# converter.net
KiCad netlist of a schematic drawn in Altium Designer
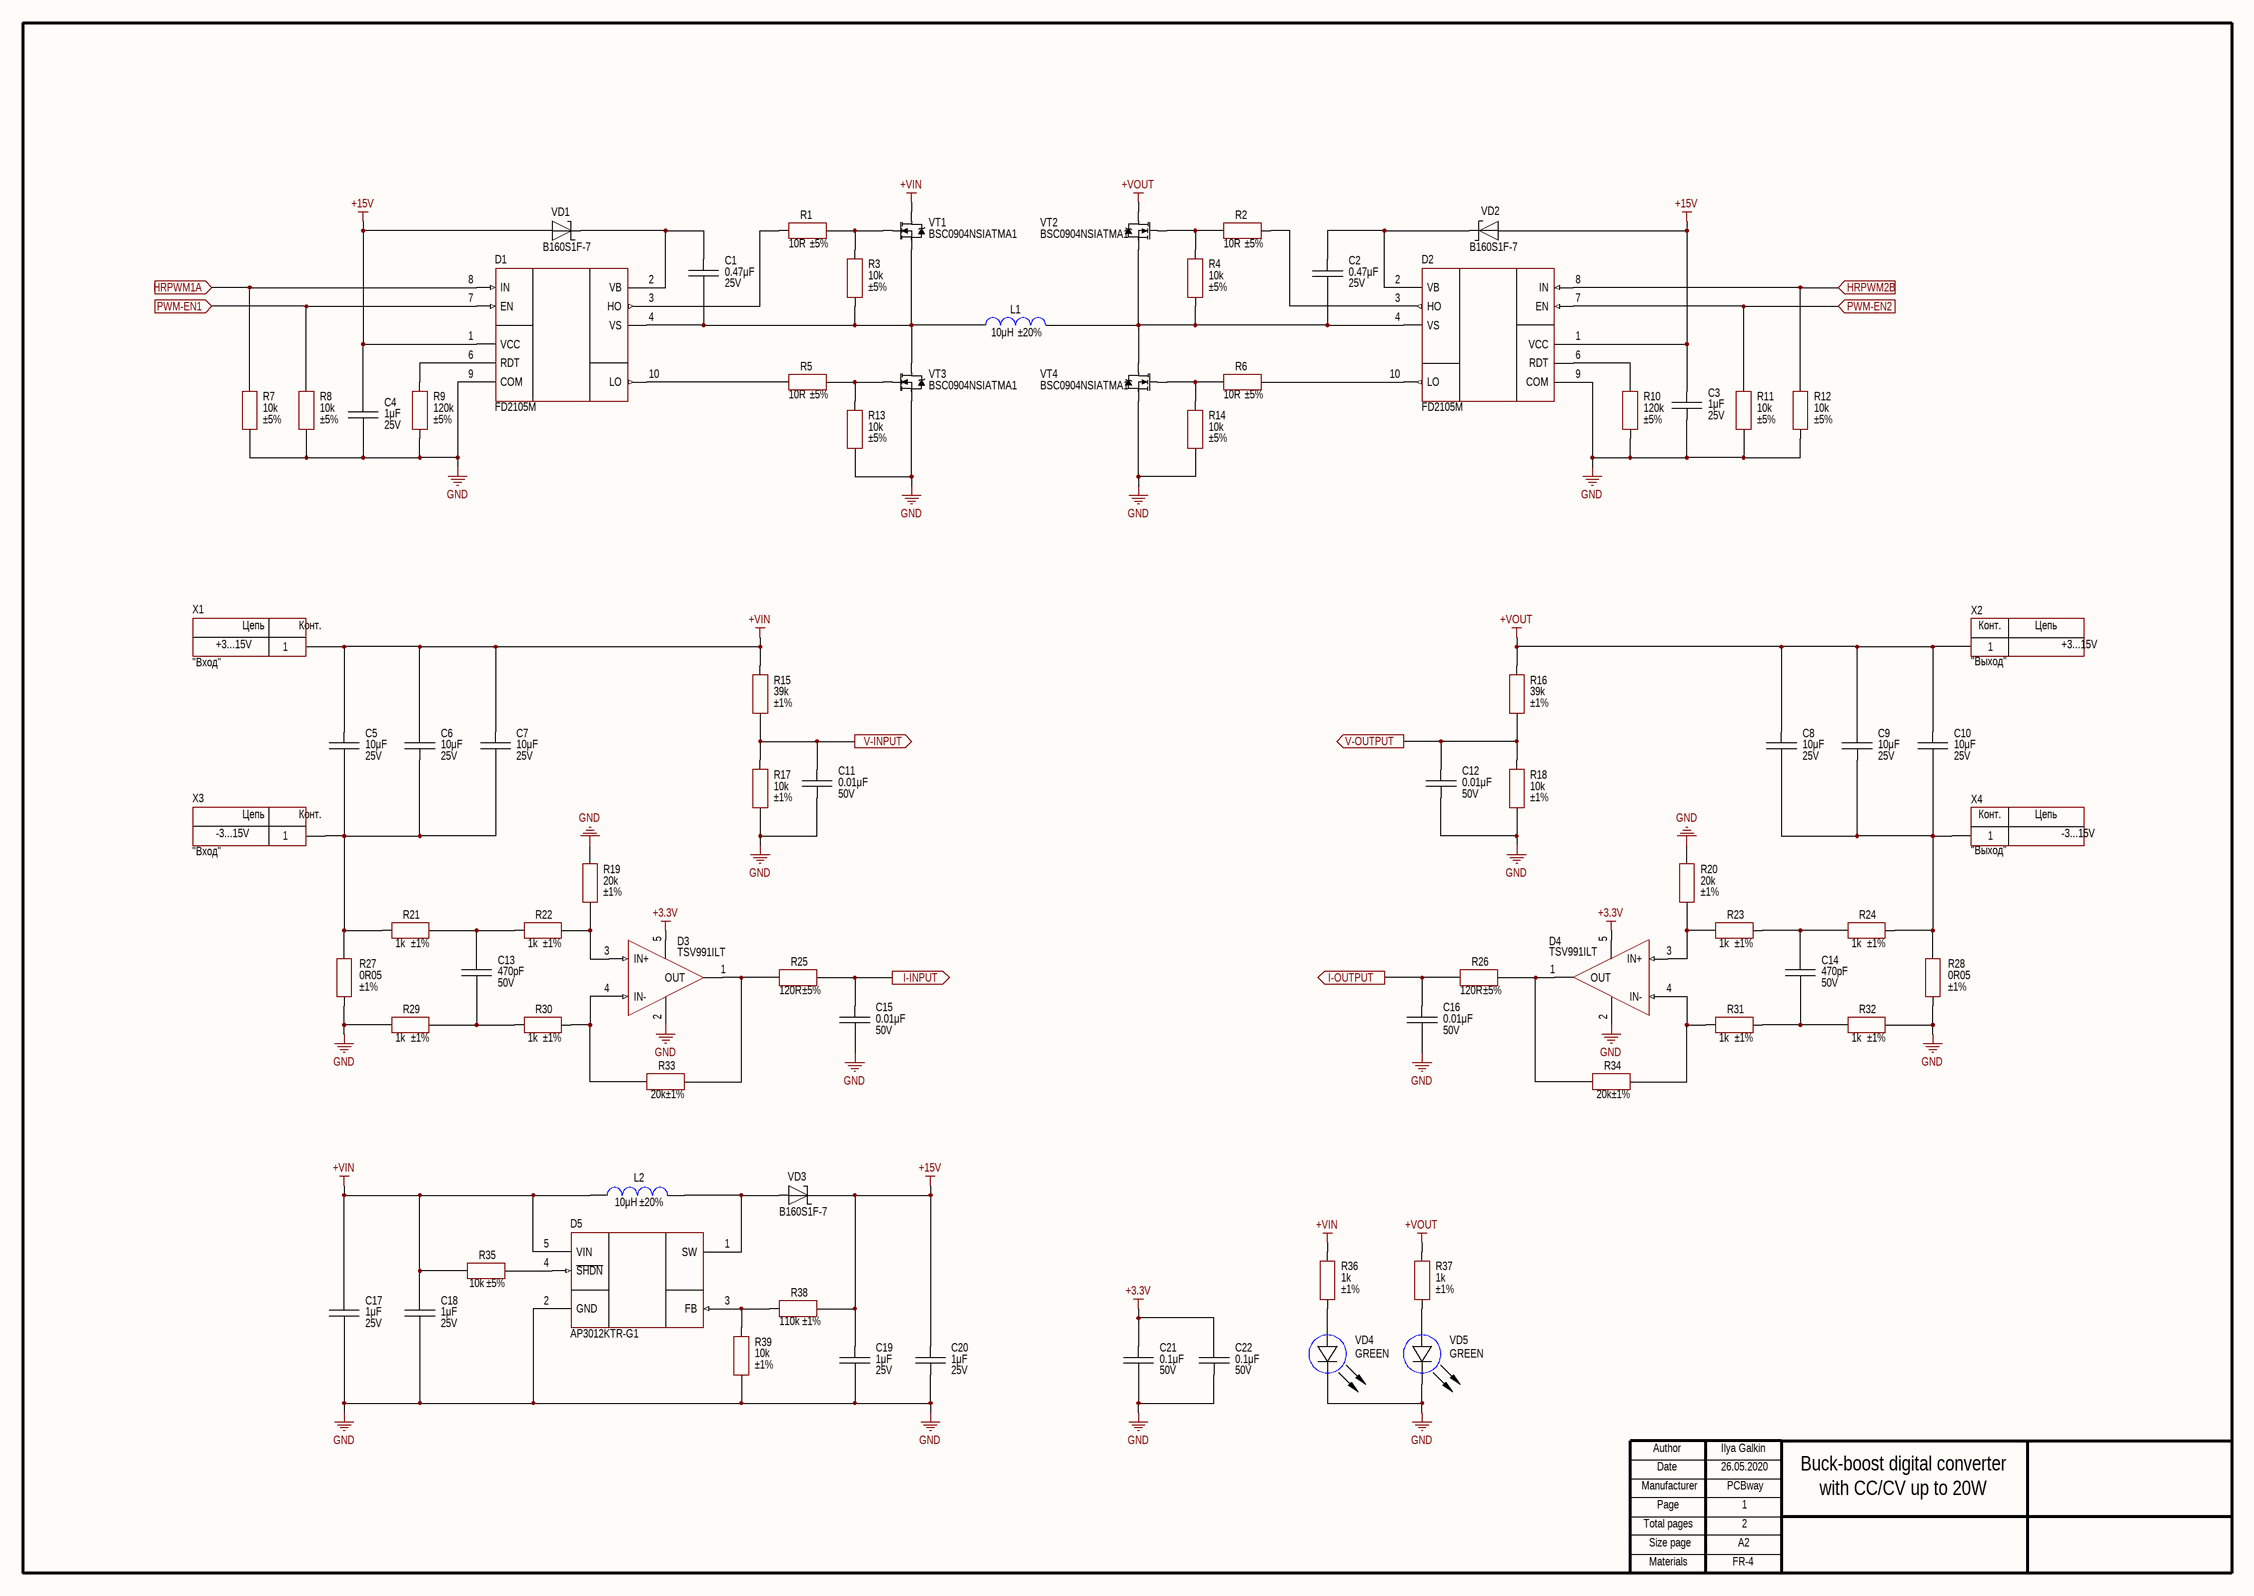
[diagram p0: converter.SchDoc]

(export (version "E")
  (design (tool "Eeschema 10.0.6"))
  (components
    (comp (ref "C1")
      (value "0.47μF")
      (footprint "CAP: 0805")
      (fields
        (field (name "MANUFACTURER") "Samsung")
        (field (name "PARTNUMBER") "CL21B474KAFNNNG")
        (field (name "VALUEMANUFACTURERPARTNUMBER") "Ceramic capacitor, 0.47μF, X7R, ±10%, 25V, 0805, -55...+125°C")
        (field (name "VOLTAGE") "25V")
      )
      (libsource (lib "Capacitor") (part "Ceramic_0805"))
    )
    (comp (ref "C2")
      (value "0.47μF")
      (footprint "CAP: 0805")
      (fields
        (field (name "MANUFACTURER") "Samsung")
        (field (name "PARTNUMBER") "CL21B474KAFNNNG")
        (field (name "VALUEMANUFACTURERPARTNUMBER") "Ceramic capacitor, 0.47μF, X7R, ±10%, 25V, 0805, -55...+125°C")
        (field (name "VOLTAGE") "25V")
      )
      (libsource (lib "Capacitor") (part "Ceramic_0805"))
    )
    (comp (ref "C3")
      (value "1μF")
      (footprint "CAP: 0603")
      (fields
        (field (name "MANUFACTURER") "Samsung")
        (field (name "PARTNUMBER") "CL10B105KA8NNNC")
        (field (name "VALUEMANUFACTURERPARTNUMBER") "Ceramic capacitor, 1μF, X7R, ±10%, 25V, 0603, -55...+125°C")
        (field (name "VOLTAGE") "25V")
      )
      (libsource (lib "Capacitor") (part "Ceramic_0603"))
    )
    (comp (ref "C4")
      (value "1μF")
      (footprint "CAP: 0603")
      (fields
        (field (name "MANUFACTURER") "Samsung")
        (field (name "PARTNUMBER") "CL10B105KA8NNNC")
        (field (name "VALUEMANUFACTURERPARTNUMBER") "Ceramic capacitor, 1μF, X7R, ±10%, 25V, 0603, -55...+125°C")
        (field (name "VOLTAGE") "25V")
      )
      (libsource (lib "Capacitor") (part "Ceramic_0603"))
    )
    (comp (ref "C5")
      (value "10μF")
      (footprint "CAP: 1210")
      (fields
        (field (name "MANUFACTURER") "Samsung")
        (field (name "PARTNUMBER") "CL32B106KAJNNNE")
        (field (name "VALUEMANUFACTURERPARTNUMBER") "Ceramic capacitor, 10μF, X7R, ±10%, 25V, 1210, -55...+125°C")
        (field (name "VOLTAGE") "25V")
      )
      (libsource (lib "Capacitor") (part "Ceramic_1210"))
    )
    (comp (ref "C6")
      (value "10μF")
      (footprint "CAP: 1210")
      (fields
        (field (name "MANUFACTURER") "Samsung")
        (field (name "PARTNUMBER") "CL32B106KAJNNNE")
        (field (name "VALUEMANUFACTURERPARTNUMBER") "Ceramic capacitor, 10μF, X7R, ±10%, 25V, 1210, -55...+125°C")
        (field (name "VOLTAGE") "25V")
      )
      (libsource (lib "Capacitor") (part "Ceramic_1210"))
    )
    (comp (ref "C7")
      (value "10μF")
      (footprint "CAP: 1210")
      (fields
        (field (name "MANUFACTURER") "Samsung")
        (field (name "PARTNUMBER") "CL32B106KAJNNNE")
        (field (name "VALUEMANUFACTURERPARTNUMBER") "Ceramic capacitor, 10μF, X7R, ±10%, 25V, 1210, -55...+125°C")
        (field (name "VOLTAGE") "25V")
      )
      (libsource (lib "Capacitor") (part "Ceramic_1210"))
    )
    (comp (ref "C8")
      (value "10μF")
      (footprint "CAP: 1210")
      (fields
        (field (name "MANUFACTURER") "Samsung")
        (field (name "PARTNUMBER") "CL32B106KAJNNNE")
        (field (name "VALUEMANUFACTURERPARTNUMBER") "Ceramic capacitor, 10μF, X7R, ±10%, 25V, 1210, -55...+125°C")
        (field (name "VOLTAGE") "25V")
      )
      (libsource (lib "Capacitor") (part "Ceramic_1210"))
    )
    (comp (ref "C9")
      (value "10μF")
      (footprint "CAP: 1210")
      (fields
        (field (name "MANUFACTURER") "Samsung")
        (field (name "PARTNUMBER") "CL32B106KAJNNNE")
        (field (name "VALUEMANUFACTURERPARTNUMBER") "Ceramic capacitor, 10μF, X7R, ±10%, 25V, 1210, -55...+125°C")
        (field (name "VOLTAGE") "25V")
      )
      (libsource (lib "Capacitor") (part "Ceramic_1210"))
    )
    (comp (ref "C10")
      (value "10μF")
      (footprint "CAP: 1210")
      (fields
        (field (name "MANUFACTURER") "Samsung")
        (field (name "PARTNUMBER") "CL32B106KAJNNNE")
        (field (name "VALUEMANUFACTURERPARTNUMBER") "Ceramic capacitor, 10μF, X7R, ±10%, 25V, 1210, -55...+125°C")
        (field (name "VOLTAGE") "25V")
      )
      (libsource (lib "Capacitor") (part "Ceramic_1210"))
    )
    (comp (ref "C11")
      (value "0.01μF")
      (footprint "CAP: 0603")
      (fields
        (field (name "MANUFACTURER") "Yageo")
        (field (name "PARTNUMBER") "CL10B103KB8NNNC")
        (field (name "VALUEMANUFACTURERPARTNUMBER") "Ceramic capacitor, 0.01μF, X7R, ±10%, 50V, 0603, -55...+125°C")
        (field (name "VOLTAGE") "50V")
      )
      (libsource (lib "Capacitor") (part "Ceramic_0603"))
    )
    (comp (ref "C12")
      (value "0.01μF")
      (footprint "CAP: 0603")
      (fields
        (field (name "MANUFACTURER") "Yageo")
        (field (name "PARTNUMBER") "CL10B103KB8NNNC")
        (field (name "VALUEMANUFACTURERPARTNUMBER") "Ceramic capacitor, 0.01μF, X7R, ±10%, 50V, 0603, -55...+125°C")
        (field (name "VOLTAGE") "50V")
      )
      (libsource (lib "Capacitor") (part "Ceramic_0603"))
    )
    (comp (ref "C13")
      (value "470pF")
      (footprint "CAP: 0603")
      (fields
        (field (name "MANUFACTURER") "Yageo")
        (field (name "PARTNUMBER") "CL10C471JB8NNNC")
        (field (name "VALUEMANUFACTURERPARTNUMBER") "Ceramic capacitor, 470pF, NPO, ±5%, 50V, 0603, -55...+125°C")
        (field (name "VOLTAGE") "50V")
      )
      (libsource (lib "Capacitor") (part "Ceramic_0603"))
    )
    (comp (ref "C14")
      (value "470pF")
      (footprint "CAP: 0603")
      (fields
        (field (name "MANUFACTURER") "Yageo")
        (field (name "PARTNUMBER") "CL10C471JB8NNNC")
        (field (name "VALUEMANUFACTURERPARTNUMBER") "Ceramic capacitor, 470pF, NPO, ±5%, 50V, 0603, -55...+125°C")
        (field (name "VOLTAGE") "50V")
      )
      (libsource (lib "Capacitor") (part "Ceramic_0603"))
    )
    (comp (ref "C15")
      (value "0.01μF")
      (footprint "CAP: 0603")
      (fields
        (field (name "MANUFACTURER") "Yageo")
        (field (name "PARTNUMBER") "CL10B103KB8NNNC")
        (field (name "VALUEMANUFACTURERPARTNUMBER") "Ceramic capacitor, 0.01μF, X7R, ±10%, 50V, 0603, -55...+125°C")
        (field (name "VOLTAGE") "50V")
      )
      (libsource (lib "Capacitor") (part "Ceramic_0603"))
    )
    (comp (ref "C16")
      (value "0.01μF")
      (footprint "CAP: 0603")
      (fields
        (field (name "MANUFACTURER") "Yageo")
        (field (name "PARTNUMBER") "CL10B103KB8NNNC")
        (field (name "VALUEMANUFACTURERPARTNUMBER") "Ceramic capacitor, 0.01μF, X7R, ±10%, 50V, 0603, -55...+125°C")
        (field (name "VOLTAGE") "50V")
      )
      (libsource (lib "Capacitor") (part "Ceramic_0603"))
    )
    (comp (ref "C17")
      (value "1μF")
      (footprint "CAP: 0603")
      (fields
        (field (name "MANUFACTURER") "Samsung")
        (field (name "PARTNUMBER") "CL10B105KA8NNNC")
        (field (name "VALUEMANUFACTURERPARTNUMBER") "Ceramic capacitor, 1μF, X7R, ±10%, 25V, 0603, -55...+125°C")
        (field (name "VOLTAGE") "25V")
      )
      (libsource (lib "Capacitor") (part "Ceramic_0603"))
    )
    (comp (ref "C18")
      (value "1μF")
      (footprint "CAP: 0603")
      (fields
        (field (name "MANUFACTURER") "Samsung")
        (field (name "PARTNUMBER") "CL10B105KA8NNNC")
        (field (name "VALUEMANUFACTURERPARTNUMBER") "Ceramic capacitor, 1μF, X7R, ±10%, 25V, 0603, -55...+125°C")
        (field (name "VOLTAGE") "25V")
      )
      (libsource (lib "Capacitor") (part "Ceramic_0603"))
    )
    (comp (ref "C19")
      (value "1μF")
      (footprint "CAP: 0603")
      (fields
        (field (name "MANUFACTURER") "Samsung")
        (field (name "PARTNUMBER") "CL10B105KA8NNNC")
        (field (name "VALUEMANUFACTURERPARTNUMBER") "Ceramic capacitor, 1μF, X7R, ±10%, 25V, 0603, -55...+125°C")
        (field (name "VOLTAGE") "25V")
      )
      (libsource (lib "Capacitor") (part "Ceramic_0603"))
    )
    (comp (ref "C20")
      (value "1μF")
      (footprint "CAP: 0603")
      (fields
        (field (name "MANUFACTURER") "Samsung")
        (field (name "PARTNUMBER") "CL10B105KA8NNNC")
        (field (name "VALUEMANUFACTURERPARTNUMBER") "Ceramic capacitor, 1μF, X7R, ±10%, 25V, 0603, -55...+125°C")
        (field (name "VOLTAGE") "25V")
      )
      (libsource (lib "Capacitor") (part "Ceramic_0603"))
    )
    (comp (ref "C21")
      (value "0.1μF")
      (footprint "CAP: 0603")
      (fields
        (field (name "MANUFACTURER") "Yageo")
        (field (name "PARTNUMBER") "CL10B104KB8WPND")
        (field (name "VALUEMANUFACTURERPARTNUMBER") "Ceramic capacitor, 0.1μF, X7R, ±10%, 50V, 0603, -55...+125°C")
        (field (name "VOLTAGE") "50V")
      )
      (libsource (lib "Capacitor") (part "Ceramic_0603"))
    )
    (comp (ref "C22")
      (value "0.1μF")
      (footprint "CAP: 0603")
      (fields
        (field (name "MANUFACTURER") "Yageo")
        (field (name "PARTNUMBER") "CL10B104KB8WPND")
        (field (name "VALUEMANUFACTURERPARTNUMBER") "Ceramic capacitor, 0.1μF, X7R, ±10%, 50V, 0603, -55...+125°C")
        (field (name "VOLTAGE") "50V")
      )
      (libsource (lib "Capacitor") (part "Ceramic_0603"))
    )
    (comp (ref "D1")
      (value "~")
      (footprint "10-TSSOP")
      (description "Gate driver")
      (fields
        (field (name "MANUFACTURER") "Fortior Tech")
        (field (name "VALUEMANUFACTURERPARTNUMBER") "Half-bridge gate driver, 40V, +1.2A/-1.8A, Complementary, supply 3...21V, -40...+125°C, 10-MSOP")
        (field (name "PARTNUMBER") "FD2105M")
      )
      (libsource (lib "") (part "FD2105M_1"))
    )
    (comp (ref "D2")
      (value "~")
      (footprint "10-TSSOP")
      (description "Gate driver")
      (fields
        (field (name "MANUFACTURER") "Fortior Tech")
        (field (name "VALUEMANUFACTURERPARTNUMBER") "Half-bridge gate driver, 40V, +1.2A/-1.8A, Complementary, supply 3...21V, -40...+125°C, 10-MSOP")
        (field (name "PARTNUMBER") "FD2105M")
      )
      (libsource (lib "IC. Gate driver") (part "FD2105M"))
    )
    (comp (ref "D3")
      (value "~")
      (footprint "SOT23-5")
      (description "OP amplifier")
      (fields
        (field (name "MANUFACTURER") "STMicroelectronics")
        (field (name "VALUEMANUFACTURERPARTNUMBER") "IC op amplifier, Rail-to-Rail, 20 MHz, 2.7...5.5V, -40...+125°C, SOT23-5")
        (field (name "PARTNUMBER") "TSV991ILT")
      )
      (libsource (lib "IC. Amplifier") (part "TSV991ILT"))
    )
    (comp (ref "D4")
      (value "~")
      (footprint "SOT23-5")
      (description "OP amplifier")
      (fields
        (field (name "MANUFACTURER") "STMicroelectronics")
        (field (name "VALUEMANUFACTURERPARTNUMBER") "IC op amplifier, Rail-to-Rail, 20 MHz, 2.7...5.5V, -40...+125°C, SOT23-5")
        (field (name "PARTNUMBER") "TSV991ILT")
      )
      (libsource (lib "IC. Amplifier") (part "TSV991ILT"))
    )
    (comp (ref "D5")
      (value "~")
      (footprint "SOT23-5")
      (description "Boost converter")
      (fields
        (field (name "MANUFACTURER") "Diodes Incorporated")
        (field (name "VALUEMANUFACTURERPARTNUMBER") "DC/DC boost converter, input 2.6...16V, 1.5MHz, output 3...29V, 0.5A, -40...+85°C, SOT23-5")
        (field (name "PARTNUMBER") "AP3012KTR-G1")
      )
      (libsource (lib "IC. Power supply") (part "AP3012KTR-G1"))
    )
    (comp (ref "L1")
      (value "10μH")
      (footprint "IND: SRP1038C")
      (fields
        (field (name "MANUFACTURER") "Bourns")
        (field (name "PARTNUMBER") "SRP1038C-100M")
        (field (name "VALUEMANUFACTURERPARTNUMBER") "Fixed inductor, 10μH, ±20%, SRP1038C, 8.5A, -40...+125°C")
        (field (name "TOLERANCE") "±20%")
      )
      (libsource (lib "Inductor") (part "Inductor_SRP1038C"))
    )
    (comp (ref "L2")
      (value "10μH")
      (footprint "IND: SDR0403")
      (fields
        (field (name "MANUFACTURER") "Bourns")
        (field (name "PARTNUMBER") "SDR0403-100ML")
        (field (name "VALUEMANUFACTURERPARTNUMBER") "Fixed inductor, 10μH, ±20%, SDR0403, 1.15A, -40...+125°C")
        (field (name "TOLERANCE") "±20%")
      )
      (libsource (lib "Inductor") (part "Inductor_SDR0403"))
    )
    (comp (ref "R1")
      (value "10R")
      (footprint "RES: 0603")
      (fields
        (field (name "MANUFACTURER") "Yageo")
        (field (name "PARTNUMBER") "RC0603JR-0710RL")
        (field (name "VALUEMANUFACTURERPARTNUMBER") "Resistor film, 10R, ±5%, 0603, 0.1W, -55...+125°C")
        (field (name "TOLERANCE") "±5%")
      )
      (libsource (lib "") (part "Resistor_0603_2"))
    )
    (comp (ref "R2")
      (value "10R")
      (footprint "RES: 0603")
      (fields
        (field (name "MANUFACTURER") "Yageo")
        (field (name "PARTNUMBER") "RC0603JR-0710RL")
        (field (name "VALUEMANUFACTURERPARTNUMBER") "Resistor film, 10R, ±5%, 0603, 0.1W, -55...+125°C")
        (field (name "TOLERANCE") "±5%")
      )
      (libsource (lib "") (part "Resistor_0603_2"))
    )
    (comp (ref "R3")
      (value "10k")
      (footprint "RES: 0603")
      (fields
        (field (name "MANUFACTURER") "Yageo")
        (field (name "PARTNUMBER") "RC0603JR-0710KL")
        (field (name "VALUEMANUFACTURERPARTNUMBER") "Resistor film, 10k, ±5%, 0603, 0.1W, -55...+125°C")
        (field (name "TOLERANCE") "±5%")
      )
      (libsource (lib "Resistor") (part "Resistor_0603"))
    )
    (comp (ref "R4")
      (value "10k")
      (footprint "RES: 0603")
      (fields
        (field (name "MANUFACTURER") "Yageo")
        (field (name "PARTNUMBER") "RC0603JR-0710KL")
        (field (name "VALUEMANUFACTURERPARTNUMBER") "Resistor film, 10k, ±5%, 0603, 0.1W, -55...+125°C")
        (field (name "TOLERANCE") "±5%")
      )
      (libsource (lib "Resistor") (part "Resistor_0603"))
    )
    (comp (ref "R5")
      (value "10R")
      (footprint "RES: 0603")
      (fields
        (field (name "MANUFACTURER") "Yageo")
        (field (name "PARTNUMBER") "RC0603JR-0710RL")
        (field (name "VALUEMANUFACTURERPARTNUMBER") "Resistor film, 10R, ±5%, 0603, 0.1W, -55...+125°C")
        (field (name "TOLERANCE") "±5%")
      )
      (libsource (lib "") (part "Resistor_0603_2"))
    )
    (comp (ref "R6")
      (value "10R")
      (footprint "RES: 0603")
      (fields
        (field (name "MANUFACTURER") "Yageo")
        (field (name "PARTNUMBER") "RC0603JR-0710RL")
        (field (name "VALUEMANUFACTURERPARTNUMBER") "Resistor film, 10R, ±5%, 0603, 0.1W, -55...+125°C")
        (field (name "TOLERANCE") "±5%")
      )
      (libsource (lib "") (part "Resistor_0603_2"))
    )
    (comp (ref "R7")
      (value "10k")
      (footprint "RES: 0603")
      (fields
        (field (name "MANUFACTURER") "Yageo")
        (field (name "PARTNUMBER") "RC0603JR-0710KL")
        (field (name "VALUEMANUFACTURERPARTNUMBER") "Resistor film, 10k, ±5%, 0603, 0.1W, -55...+125°C")
        (field (name "TOLERANCE") "±5%")
      )
      (libsource (lib "Resistor") (part "Resistor_0603"))
    )
    (comp (ref "R8")
      (value "10k")
      (footprint "RES: 0603")
      (fields
        (field (name "MANUFACTURER") "Yageo")
        (field (name "PARTNUMBER") "RC0603JR-0710KL")
        (field (name "VALUEMANUFACTURERPARTNUMBER") "Resistor film, 10k, ±5%, 0603, 0.1W, -55...+125°C")
        (field (name "TOLERANCE") "±5%")
      )
      (libsource (lib "Resistor") (part "Resistor_0603"))
    )
    (comp (ref "R9")
      (value "120k")
      (footprint "RES: 0603")
      (fields
        (field (name "MANUFACTURER") "Yageo")
        (field (name "PARTNUMBER") "RC0603JR-07120KL")
        (field (name "VALUEMANUFACTURERPARTNUMBER") "Resistor film, 120k, ±5%, 0603, 0.1W, -55...+125°C")
        (field (name "TOLERANCE") "±5%")
      )
      (libsource (lib "Resistor") (part "Resistor_0603"))
    )
    (comp (ref "R10")
      (value "120k")
      (footprint "RES: 0603")
      (fields
        (field (name "MANUFACTURER") "Yageo")
        (field (name "PARTNUMBER") "RC0603JR-07120KL")
        (field (name "VALUEMANUFACTURERPARTNUMBER") "Resistor film, 120k, ±5%, 0603, 0.1W, -55...+125°C")
        (field (name "TOLERANCE") "±5%")
      )
      (libsource (lib "Resistor") (part "Resistor_0603"))
    )
    (comp (ref "R11")
      (value "10k")
      (footprint "RES: 0603")
      (fields
        (field (name "MANUFACTURER") "Yageo")
        (field (name "PARTNUMBER") "RC0603JR-0710KL")
        (field (name "VALUEMANUFACTURERPARTNUMBER") "Resistor film, 10k, ±5%, 0603, 0.1W, -55...+125°C")
        (field (name "TOLERANCE") "±5%")
      )
      (libsource (lib "Resistor") (part "Resistor_0603"))
    )
    (comp (ref "R12")
      (value "10k")
      (footprint "RES: 0603")
      (fields
        (field (name "MANUFACTURER") "Yageo")
        (field (name "PARTNUMBER") "RC0603JR-0710KL")
        (field (name "VALUEMANUFACTURERPARTNUMBER") "Resistor film, 10k, ±5%, 0603, 0.1W, -55...+125°C")
        (field (name "TOLERANCE") "±5%")
      )
      (libsource (lib "Resistor") (part "Resistor_0603"))
    )
    (comp (ref "R13")
      (value "10k")
      (footprint "RES: 0603")
      (fields
        (field (name "MANUFACTURER") "Yageo")
        (field (name "PARTNUMBER") "RC0603JR-0710KL")
        (field (name "VALUEMANUFACTURERPARTNUMBER") "Resistor film, 10k, ±5%, 0603, 0.1W, -55...+125°C")
        (field (name "TOLERANCE") "±5%")
      )
      (libsource (lib "Resistor") (part "Resistor_0603"))
    )
    (comp (ref "R14")
      (value "10k")
      (footprint "RES: 0603")
      (fields
        (field (name "MANUFACTURER") "Yageo")
        (field (name "PARTNUMBER") "RC0603JR-0710KL")
        (field (name "VALUEMANUFACTURERPARTNUMBER") "Resistor film, 10k, ±5%, 0603, 0.1W, -55...+125°C")
        (field (name "TOLERANCE") "±5%")
      )
      (libsource (lib "Resistor") (part "Resistor_0603"))
    )
    (comp (ref "R15")
      (value "39k")
      (footprint "RES: 0603")
      (fields
        (field (name "MANUFACTURER") "Yageo")
        (field (name "PARTNUMBER") "RC0603FR-0739KL")
        (field (name "VALUEMANUFACTURERPARTNUMBER") "Resistor film, 39k, ±1%, 0603, 0.1W, -55...+125°C")
        (field (name "TOLERANCE") "±1%")
      )
      (libsource (lib "Resistor") (part "Resistor_0603"))
    )
    (comp (ref "R16")
      (value "39k")
      (footprint "RES: 0603")
      (fields
        (field (name "MANUFACTURER") "Yageo")
        (field (name "PARTNUMBER") "RC0603FR-0739KL")
        (field (name "VALUEMANUFACTURERPARTNUMBER") "Resistor film, 39k, ±1%, 0603, 0.1W, -55...+125°C")
        (field (name "TOLERANCE") "±1%")
      )
      (libsource (lib "Resistor") (part "Resistor_0603"))
    )
    (comp (ref "R17")
      (value "10k")
      (footprint "RES: 0603")
      (fields
        (field (name "MANUFACTURER") "Yageo")
        (field (name "PARTNUMBER") "RC0603FR-0710KL")
        (field (name "VALUEMANUFACTURERPARTNUMBER") "Resistor film, 10k, ±1%, 0603, 0.1W, -55...+125°C")
        (field (name "TOLERANCE") "±1%")
      )
      (libsource (lib "Resistor") (part "Resistor_0603"))
    )
    (comp (ref "R18")
      (value "10k")
      (footprint "RES: 0603")
      (fields
        (field (name "MANUFACTURER") "Yageo")
        (field (name "PARTNUMBER") "RC0603FR-0710KL")
        (field (name "VALUEMANUFACTURERPARTNUMBER") "Resistor film, 10k, ±1%, 0603, 0.1W, -55...+125°C")
        (field (name "TOLERANCE") "±1%")
      )
      (libsource (lib "Resistor") (part "Resistor_0603"))
    )
    (comp (ref "R19")
      (value "20k")
      (footprint "RES: 0603")
      (fields
        (field (name "MANUFACTURER") "Yageo")
        (field (name "PARTNUMBER") "RC0603FR-0720KL")
        (field (name "VALUEMANUFACTURERPARTNUMBER") "Resistor film, 20k, ±1%, 0603, 0.1W, -55...+125°C")
        (field (name "TOLERANCE") "±1%")
      )
      (libsource (lib "Resistor") (part "Resistor_0603"))
    )
    (comp (ref "R20")
      (value "20k")
      (footprint "RES: 0603")
      (fields
        (field (name "MANUFACTURER") "Yageo")
        (field (name "PARTNUMBER") "RC0603FR-0720KL")
        (field (name "VALUEMANUFACTURERPARTNUMBER") "Resistor film, 20k, ±1%, 0603, 0.1W, -55...+125°C")
        (field (name "TOLERANCE") "±1%")
      )
      (libsource (lib "Resistor") (part "Resistor_0603"))
    )
    (comp (ref "R21")
      (value "1k")
      (footprint "RES: 0603")
      (fields
        (field (name "MANUFACTURER") "Yageo")
        (field (name "PARTNUMBER") "RC0603FR-071KL")
        (field (name "VALUEMANUFACTURERPARTNUMBER") "Resistor film, 1k, ±1%, 0603, 0.1W, -55...+125°C")
        (field (name "TOLERANCE") "±1%")
      )
      (libsource (lib "") (part "Resistor_0603_2"))
    )
    (comp (ref "R22")
      (value "1k")
      (footprint "RES: 0603")
      (fields
        (field (name "MANUFACTURER") "Yageo")
        (field (name "PARTNUMBER") "RC0603FR-071KL")
        (field (name "VALUEMANUFACTURERPARTNUMBER") "Resistor film, 1k, ±1%, 0603, 0.1W, -55...+125°C")
        (field (name "TOLERANCE") "±1%")
      )
      (libsource (lib "") (part "Resistor_0603_2"))
    )
    (comp (ref "R23")
      (value "1k")
      (footprint "RES: 0603")
      (fields
        (field (name "MANUFACTURER") "Yageo")
        (field (name "PARTNUMBER") "RC0603FR-071KL")
        (field (name "VALUEMANUFACTURERPARTNUMBER") "Resistor film, 1k, ±1%, 0603, 0.1W, -55...+125°C")
        (field (name "TOLERANCE") "±1%")
      )
      (libsource (lib "") (part "Resistor_0603_2"))
    )
    (comp (ref "R24")
      (value "1k")
      (footprint "RES: 0603")
      (fields
        (field (name "MANUFACTURER") "Yageo")
        (field (name "PARTNUMBER") "RC0603FR-071KL")
        (field (name "VALUEMANUFACTURERPARTNUMBER") "Resistor film, 1k, ±1%, 0603, 0.1W, -55...+125°C")
        (field (name "TOLERANCE") "±1%")
      )
      (libsource (lib "") (part "Resistor_0603_2"))
    )
    (comp (ref "R25")
      (value "120R")
      (footprint "RES: 0603")
      (fields
        (field (name "MANUFACTURER") "Yageo")
        (field (name "PARTNUMBER") "RC0603JR-07120RL")
        (field (name "VALUEMANUFACTURERPARTNUMBER") "Resistor film, 120R, ±5%, 0603, 0.1W, -55...+125°C")
        (field (name "TOLERANCE") "±5%")
      )
      (libsource (lib "") (part "Resistor_0603_2"))
    )
    (comp (ref "R26")
      (value "120R")
      (footprint "RES: 0603")
      (fields
        (field (name "MANUFACTURER") "Yageo")
        (field (name "PARTNUMBER") "RC0603JR-07120RL")
        (field (name "VALUEMANUFACTURERPARTNUMBER") "Resistor film, 120R, ±5%, 0603, 0.1W, -55...+125°C")
        (field (name "TOLERANCE") "±5%")
      )
      (libsource (lib "") (part "Resistor_0603_2"))
    )
    (comp (ref "R27")
      (value "0R05")
      (footprint "RES: CSS2H (2512)")
      (fields
        (field (name "MANUFACTURER") "Bourns")
        (field (name "PARTNUMBER") "CRA2512-FZ-R050ELF")
        (field (name "VALUEMANUFACTURERPARTNUMBER") "Resistor film, 0R05, ±1%, 2512, 3W, -55...+170°C")
        (field (name "TOLERANCE") "±1%")
      )
      (libsource (lib "Resistor") (part "Shunt"))
    )
    (comp (ref "R28")
      (value "0R05")
      (footprint "RES: CSS2H (2512)")
      (fields
        (field (name "MANUFACTURER") "Bourns")
        (field (name "PARTNUMBER") "CRA2512-FZ-R050ELF")
        (field (name "VALUEMANUFACTURERPARTNUMBER") "Resistor film, 0R05, ±1%, 2512, 3W, -55...+170°C")
        (field (name "TOLERANCE") "±1%")
      )
      (libsource (lib "Resistor") (part "Shunt"))
    )
    (comp (ref "R29")
      (value "1k")
      (footprint "RES: 0603")
      (fields
        (field (name "MANUFACTURER") "Yageo")
        (field (name "PARTNUMBER") "RC0603FR-071KL")
        (field (name "VALUEMANUFACTURERPARTNUMBER") "Resistor film, 1k, ±1%, 0603, 0.1W, -55...+125°C")
        (field (name "TOLERANCE") "±1%")
      )
      (libsource (lib "") (part "Resistor_0603_2"))
    )
    (comp (ref "R30")
      (value "1k")
      (footprint "RES: 0603")
      (fields
        (field (name "MANUFACTURER") "Yageo")
        (field (name "PARTNUMBER") "RC0603FR-071KL")
        (field (name "VALUEMANUFACTURERPARTNUMBER") "Resistor film, 1k, ±1%, 0603, 0.1W, -55...+125°C")
        (field (name "TOLERANCE") "±1%")
      )
      (libsource (lib "") (part "Resistor_0603_2"))
    )
    (comp (ref "R31")
      (value "1k")
      (footprint "RES: 0603")
      (fields
        (field (name "MANUFACTURER") "Yageo")
        (field (name "PARTNUMBER") "RC0603FR-071KL")
        (field (name "VALUEMANUFACTURERPARTNUMBER") "Resistor film, 1k, ±1%, 0603, 0.1W, -55...+125°C")
        (field (name "TOLERANCE") "±1%")
      )
      (libsource (lib "") (part "Resistor_0603_2"))
    )
    (comp (ref "R32")
      (value "1k")
      (footprint "RES: 0603")
      (fields
        (field (name "MANUFACTURER") "Yageo")
        (field (name "PARTNUMBER") "RC0603FR-071KL")
        (field (name "VALUEMANUFACTURERPARTNUMBER") "Resistor film, 1k, ±1%, 0603, 0.1W, -55...+125°C")
        (field (name "TOLERANCE") "±1%")
      )
      (libsource (lib "") (part "Resistor_0603_2"))
    )
    (comp (ref "R33")
      (value "20k")
      (footprint "RES: 0603")
      (fields
        (field (name "MANUFACTURER") "Yageo")
        (field (name "PARTNUMBER") "RC0603FR-0720KL")
        (field (name "VALUEMANUFACTURERPARTNUMBER") "Resistor film, 20k, ±1%, 0603, 0.1W, -55...+125°C")
        (field (name "TOLERANCE") "±1%")
      )
      (libsource (lib "") (part "Resistor_0603_2"))
    )
    (comp (ref "R34")
      (value "20k")
      (footprint "RES: 0603")
      (fields
        (field (name "MANUFACTURER") "Yageo")
        (field (name "PARTNUMBER") "RC0603FR-0720KL")
        (field (name "VALUEMANUFACTURERPARTNUMBER") "Resistor film, 20k, ±1%, 0603, 0.1W, -55...+125°C")
        (field (name "TOLERANCE") "±1%")
      )
      (libsource (lib "") (part "Resistor_0603_2"))
    )
    (comp (ref "R35")
      (value "10k")
      (footprint "RES: 0603")
      (fields
        (field (name "MANUFACTURER") "Yageo")
        (field (name "PARTNUMBER") "RC0603JR-0710KL")
        (field (name "VALUEMANUFACTURERPARTNUMBER") "Resistor film, 10k, ±5%, 0603, 0.1W, -55...+125°C")
        (field (name "TOLERANCE") "±5%")
      )
      (libsource (lib "") (part "Resistor_0603_1"))
    )
    (comp (ref "R36")
      (value "1k")
      (footprint "RES: 0603")
      (fields
        (field (name "MANUFACTURER") "Yageo")
        (field (name "PARTNUMBER") "RC0603FR-071KL")
        (field (name "VALUEMANUFACTURERPARTNUMBER") "Resistor film, 1k, ±1%, 0603, 0.1W, -55...+125°C")
        (field (name "TOLERANCE") "±1%")
      )
      (libsource (lib "Resistor") (part "Resistor_0603"))
    )
    (comp (ref "R37")
      (value "1k")
      (footprint "RES: 0603")
      (fields
        (field (name "MANUFACTURER") "Yageo")
        (field (name "PARTNUMBER") "RC0603FR-071KL")
        (field (name "VALUEMANUFACTURERPARTNUMBER") "Resistor film, 1k, ±1%, 0603, 0.1W, -55...+125°C")
        (field (name "TOLERANCE") "±1%")
      )
      (libsource (lib "Resistor") (part "Resistor_0603"))
    )
    (comp (ref "R38")
      (value "110k")
      (footprint "RES: 0603")
      (fields
        (field (name "MANUFACTURER") "Yageo")
        (field (name "PARTNUMBER") "RC0603FR-07110KL")
        (field (name "VALUEMANUFACTURERPARTNUMBER") "Resistor film, 110k, ±1%, 0603, 0.1W, -55...+125°C")
        (field (name "TOLERANCE") "±1%")
      )
      (libsource (lib "") (part "Resistor_0603_1"))
    )
    (comp (ref "R39")
      (value "10k")
      (footprint "RES: 0603")
      (fields
        (field (name "MANUFACTURER") "Yageo")
        (field (name "PARTNUMBER") "RC0603FR-0710KL")
        (field (name "VALUEMANUFACTURERPARTNUMBER") "Resistor film, 10k, ±1%, 0603, 0.1W, -55...+125°C")
        (field (name "TOLERANCE") "±1%")
      )
      (libsource (lib "Resistor") (part "Resistor_0603"))
    )
    (comp (ref "VD1")
      (value "~")
      (footprint "DIODE: SOD123F")
      (fields
        (field (name "MANUFACTURER") "Diodes Incorporated")
        (field (name "VALUEMANUFACTURERPARTNUMBER") "Schottky diode, 60B160S1F-7, 1A, 650mV, 45pF, SOD-123F, -55...+150°C")
        (field (name "VOLTAGE") "60B160S1F-7")
        (field (name "PARTNUMBER") "B160S1F-7")
      )
      (libsource (lib "Diode") (part "Schottky_single"))
    )
    (comp (ref "VD2")
      (value "~")
      (footprint "DIODE: SOD123F")
      (fields
        (field (name "MANUFACTURER") "Diodes Incorporated")
        (field (name "VALUEMANUFACTURERPARTNUMBER") "Schottky diode, 60B160S1F-7, 1A, 650mV, 45pF, SOD-123F, -55...+150°C")
        (field (name "VOLTAGE") "60B160S1F-7")
        (field (name "PARTNUMBER") "B160S1F-7")
      )
      (libsource (lib "Diode") (part "Schottky_single"))
    )
    (comp (ref "VD3")
      (value "~")
      (footprint "DIODE: SOD123F")
      (fields
        (field (name "MANUFACTURER") "Diodes Incorporated")
        (field (name "VALUEMANUFACTURERPARTNUMBER") "Schottky diode, 60B160S1F-7, 1A, 650mV, 45pF, SOD-123F, -55...+150°C")
        (field (name "VOLTAGE") "60B160S1F-7")
        (field (name "PARTNUMBER") "B160S1F-7")
      )
      (libsource (lib "Diode") (part "Schottky_single"))
    )
    (comp (ref "VD4")
      (value "~")
      (footprint "LED: 0603G")
      (fields
        (field (name "MANUFACTURER") "Wurth")
        (field (name "VALUEMANUFACTURERPARTNUMBER") "LED, 20mA, 2V, 0603, -55...+150°C")
        (field (name "PARTNUMBER") "150060VS75000")
        (field (name "COLOR") "GREEN")
      )
      (libsource (lib "Diode") (part "LED_single"))
    )
    (comp (ref "VD5")
      (value "~")
      (footprint "LED: 0603G")
      (fields
        (field (name "MANUFACTURER") "Wurth")
        (field (name "VALUEMANUFACTURERPARTNUMBER") "LED, 20mA, 2V, 0603, -55...+150°C")
        (field (name "PARTNUMBER") "150060VS75000")
        (field (name "COLOR") "GREEN")
      )
      (libsource (lib "Diode") (part "LED_single"))
    )
    (comp (ref "VT1")
      (value "~")
      (footprint "8-TDSON")
      (fields
        (field (name "MANUFACTURER") "Infineon Technologies")
        (field (name "VALUEMANUFACTURERPARTNUMBER") "MOSFET N-channel transistor, 30V, 20A, 17nC, 2.5W, 3.7mOhm, 1100pF, 8-TDSON, -55...+150°C")
        (field (name "PARTNUMBER") "BSC0904NSIATMA1")
      )
      (libsource (lib "Transistor") (part "MOSFET_N_123"))
    )
    (comp (ref "VT2")
      (value "~")
      (footprint "8-TDSON")
      (fields
        (field (name "MANUFACTURER") "Infineon Technologies")
        (field (name "VALUEMANUFACTURERPARTNUMBER") "MOSFET N-channel transistor, 30V, 20A, 17nC, 2.5W, 3.7mOhm, 1100pF, 8-TDSON, -55...+150°C")
        (field (name "PARTNUMBER") "BSC0904NSIATMA1")
      )
      (libsource (lib "Transistor") (part "MOSFET_N_123"))
    )
    (comp (ref "VT3")
      (value "~")
      (footprint "8-TDSON")
      (fields
        (field (name "MANUFACTURER") "Infineon Technologies")
        (field (name "VALUEMANUFACTURERPARTNUMBER") "MOSFET N-channel transistor, 30V, 20A, 17nC, 2.5W, 3.7mOhm, 1100pF, 8-TDSON, -55...+150°C")
        (field (name "PARTNUMBER") "BSC0904NSIATMA1")
      )
      (libsource (lib "Transistor") (part "MOSFET_N_123"))
    )
    (comp (ref "VT4")
      (value "~")
      (footprint "8-TDSON")
      (fields
        (field (name "MANUFACTURER") "Infineon Technologies")
        (field (name "VALUEMANUFACTURERPARTNUMBER") "MOSFET N-channel transistor, 30V, 20A, 17nC, 2.5W, 3.7mOhm, 1100pF, 8-TDSON, -55...+150°C")
        (field (name "PARTNUMBER") "BSC0904NSIATMA1")
      )
      (libsource (lib "Transistor") (part "MOSFET_N_123"))
    )
    (comp (ref "X1")
      (value "~")
      (footprint "CON: 8191")
      (fields
        (field (name "MANUFACTURER") "Keystone")
        (field (name "VALUEMANUFACTURERPARTNUMBER") "Power connector, 500V, 15A")
        (field (name "PARTNUMBER") "8191")
        (field (name "COMMENTTEXT") "\"Вход\"")
      )
      (libsource (lib "Connector") (part "Connector_single_power"))
    )
    (comp (ref "X2")
      (value "~")
      (footprint "CON: 8191")
      (fields
        (field (name "MANUFACTURER") "Keystone")
        (field (name "VALUEMANUFACTURERPARTNUMBER") "Power connector, 500V, 15A")
        (field (name "PARTNUMBER") "8191")
        (field (name "COMMENTTEXT") "\"Выход\"")
      )
      (libsource (lib "") (part "Connector_single_power_1"))
    )
    (comp (ref "X3")
      (value "~")
      (footprint "CON: 8191")
      (fields
        (field (name "MANUFACTURER") "Keystone")
        (field (name "VALUEMANUFACTURERPARTNUMBER") "Power connector, 500V, 15A")
        (field (name "PARTNUMBER") "8191")
        (field (name "COMMENTTEXT") "\"Вход\"")
      )
      (libsource (lib "Connector") (part "Connector_single_power"))
    )
    (comp (ref "X4")
      (value "~")
      (footprint "CON: 8191")
      (fields
        (field (name "MANUFACTURER") "Keystone")
        (field (name "VALUEMANUFACTURERPARTNUMBER") "Power connector, 500V, 15A")
        (field (name "PARTNUMBER") "8191")
        (field (name "COMMENTTEXT") "\"Выход\"")
      )
      (libsource (lib "") (part "Connector_single_power_1"))
    )
  )
  (nets
    (net (code "1") (name "+3.3V") (class "Default")
      (node (ref "C21") (pin "2") (pinfunction "2_2") (pintype "power_in"))
      (node (ref "C22") (pin "2") (pinfunction "2_2") (pintype "power_in"))
      (node (ref "D3") (pin "5") (pinfunction "V+_5") (pintype "power_in"))
      (node (ref "D4") (pin "5") (pinfunction "V+_5") (pintype "power_in"))
    )
    (net (code "2") (name "+15V") (class "Default")
      (node (ref "C19") (pin "2") (pinfunction "2_2") (pintype "power_in"))
      (node (ref "C20") (pin "2") (pinfunction "2_2") (pintype "power_in"))
      (node (ref "C3") (pin "2") (pinfunction "2_2") (pintype "power_in"))
      (node (ref "C4") (pin "2") (pinfunction "2_2") (pintype "power_in"))
      (node (ref "D1") (pin "1") (pinfunction "VCC_1") (pintype "passive"))
      (node (ref "D2") (pin "1") (pinfunction "VCC_1") (pintype "passive"))
      (node (ref "R38") (pin "1") (pinfunction "1_1") (pintype "passive"))
      (node (ref "VD1") (pin "1") (pinfunction "1_1") (pintype "passive"))
      (node (ref "VD2") (pin "1") (pinfunction "1_1") (pintype "passive"))
      (node (ref "VD3") (pin "2") (pinfunction "2_2") (pintype "passive"))
    )
    (net (code "3") (name "+VIN") (class "Default")
      (node (ref "C17") (pin "2") (pinfunction "2_2") (pintype "power_in"))
      (node (ref "C18") (pin "2") (pinfunction "2_2") (pintype "power_in"))
      (node (ref "C5") (pin "2") (pinfunction "2_2") (pintype "power_in"))
      (node (ref "C6") (pin "2") (pinfunction "2_2") (pintype "power_in"))
      (node (ref "C7") (pin "2") (pinfunction "2_2") (pintype "power_in"))
      (node (ref "D5") (pin "5") (pinfunction "VIN_5") (pintype "passive"))
      (node (ref "L2") (pin "2") (pinfunction "2_2") (pintype "passive"))
      (node (ref "R15") (pin "2") (pinfunction "2_2") (pintype "passive"))
      (node (ref "R35") (pin "2") (pinfunction "2_2") (pintype "passive"))
      (node (ref "R36") (pin "2") (pinfunction "2_2") (pintype "passive"))
      (node (ref "VT1") (pin "2") (pinfunction "D_2") (pintype "passive"))
      (node (ref "X1") (pin "1") (pinfunction "1_1") (pintype "passive"))
    )
    (net (code "4") (name "+VOUT") (class "Default")
      (node (ref "C10") (pin "2") (pinfunction "2_2") (pintype "power_in"))
      (node (ref "C8") (pin "2") (pinfunction "2_2") (pintype "power_in"))
      (node (ref "C9") (pin "2") (pinfunction "2_2") (pintype "power_in"))
      (node (ref "R16") (pin "2") (pinfunction "2_2") (pintype "passive"))
      (node (ref "R37") (pin "2") (pinfunction "2_2") (pintype "passive"))
      (node (ref "VT2") (pin "2") (pinfunction "D_2") (pintype "passive"))
      (node (ref "X2") (pin "1") (pinfunction "1_1") (pintype "passive"))
    )
    (net (code "5") (name "/HRPWM1A") (class "Default")
      (node (ref "D1") (pin "8") (pinfunction "IN_8") (pintype "input"))
      (node (ref "R7") (pin "2") (pinfunction "2_2") (pintype "passive"))
    )
    (net (code "6") (name "/HRPWM2B") (class "Default")
      (node (ref "D2") (pin "8") (pinfunction "IN_8") (pintype "input"))
      (node (ref "R12") (pin "2") (pinfunction "2_2") (pintype "passive"))
    )
    (net (code "7") (name "/I-INPUT") (class "Default")
      (node (ref "C15") (pin "2") (pinfunction "2_2") (pintype "power_in"))
      (node (ref "R25") (pin "2") (pinfunction "2_2") (pintype "passive"))
    )
    (net (code "8") (name "/I-OUTPUT") (class "Default")
      (node (ref "C16") (pin "2") (pinfunction "2_2") (pintype "power_in"))
      (node (ref "R26") (pin "1") (pinfunction "1_1") (pintype "passive"))
    )
    (net (code "9") (name "/PWM-EN1") (class "Default")
      (node (ref "D1") (pin "7") (pinfunction "EN_7") (pintype "input"))
      (node (ref "R8") (pin "2") (pinfunction "2_2") (pintype "passive"))
    )
    (net (code "10") (name "/PWM-EN2") (class "Default")
      (node (ref "D2") (pin "7") (pinfunction "EN_7") (pintype "input"))
      (node (ref "R11") (pin "2") (pinfunction "2_2") (pintype "passive"))
    )
    (net (code "11") (name "/V-INPUT") (class "Default")
      (node (ref "C11") (pin "2") (pinfunction "2_2") (pintype "power_in"))
      (node (ref "R15") (pin "1") (pinfunction "1_1") (pintype "passive"))
      (node (ref "R17") (pin "2") (pinfunction "2_2") (pintype "passive"))
    )
    (net (code "12") (name "/V-OUTPUT") (class "Default")
      (node (ref "C12") (pin "2") (pinfunction "2_2") (pintype "power_in"))
      (node (ref "R16") (pin "1") (pinfunction "1_1") (pintype "passive"))
      (node (ref "R18") (pin "2") (pinfunction "2_2") (pintype "passive"))
    )
    (net (code "13") (name "GND") (class "Default")
      (node (ref "C11") (pin "1") (pinfunction "1_1") (pintype "power_in"))
      (node (ref "C12") (pin "1") (pinfunction "1_1") (pintype "power_in"))
      (node (ref "C15") (pin "1") (pinfunction "1_1") (pintype "power_in"))
      (node (ref "C16") (pin "1") (pinfunction "1_1") (pintype "power_in"))
      (node (ref "C17") (pin "1") (pinfunction "1_1") (pintype "power_in"))
      (node (ref "C18") (pin "1") (pinfunction "1_1") (pintype "power_in"))
      (node (ref "C19") (pin "1") (pinfunction "1_1") (pintype "power_in"))
      (node (ref "C20") (pin "1") (pinfunction "1_1") (pintype "power_in"))
      (node (ref "C21") (pin "1") (pinfunction "1_1") (pintype "power_in"))
      (node (ref "C22") (pin "1") (pinfunction "1_1") (pintype "power_in"))
      (node (ref "C3") (pin "1") (pinfunction "1_1") (pintype "power_in"))
      (node (ref "C4") (pin "1") (pinfunction "1_1") (pintype "power_in"))
      (node (ref "D1") (pin "9") (pinfunction "COM_9") (pintype "passive"))
      (node (ref "D2") (pin "9") (pinfunction "COM_9") (pintype "passive"))
      (node (ref "D3") (pin "2") (pinfunction "V-_2") (pintype "power_in"))
      (node (ref "D4") (pin "2") (pinfunction "V-_2") (pintype "power_in"))
      (node (ref "D5") (pin "2") (pinfunction "GND_2") (pintype "passive"))
      (node (ref "R10") (pin "1") (pinfunction "1_1") (pintype "passive"))
      (node (ref "R11") (pin "1") (pinfunction "1_1") (pintype "passive"))
      (node (ref "R12") (pin "1") (pinfunction "1_1") (pintype "passive"))
      (node (ref "R13") (pin "1") (pinfunction "1_1") (pintype "passive"))
      (node (ref "R14") (pin "1") (pinfunction "1_1") (pintype "passive"))
      (node (ref "R17") (pin "1") (pinfunction "1_1") (pintype "passive"))
      (node (ref "R18") (pin "1") (pinfunction "1_1") (pintype "passive"))
      (node (ref "R19") (pin "2") (pinfunction "2_2") (pintype "passive"))
      (node (ref "R20") (pin "2") (pinfunction "2_2") (pintype "passive"))
      (node (ref "R27") (pin "1") (pinfunction "1_1") (pintype "passive"))
      (node (ref "R28") (pin "1") (pinfunction "1_1") (pintype "passive"))
      (node (ref "R29") (pin "1") (pinfunction "1_1") (pintype "passive"))
      (node (ref "R32") (pin "2") (pinfunction "2_2") (pintype "passive"))
      (node (ref "R39") (pin "1") (pinfunction "1_1") (pintype "passive"))
      (node (ref "R7") (pin "1") (pinfunction "1_1") (pintype "passive"))
      (node (ref "R8") (pin "1") (pinfunction "1_1") (pintype "passive"))
      (node (ref "R9") (pin "1") (pinfunction "1_1") (pintype "passive"))
      (node (ref "VD4") (pin "2") (pinfunction "C_2") (pintype "passive"))
      (node (ref "VD5") (pin "2") (pinfunction "C_2") (pintype "passive"))
      (node (ref "VT3") (pin "3") (pinfunction "S_3") (pintype "passive"))
      (node (ref "VT4") (pin "3") (pinfunction "S_3") (pintype "passive"))
    )
    (net (code "14") (name "Net-(C5-Pad1)") (class "Default")
      (node (ref "C5") (pin "1") (pinfunction "1_1") (pintype "power_in"))
      (node (ref "C6") (pin "1") (pinfunction "1_1") (pintype "power_in"))
      (node (ref "C7") (pin "1") (pinfunction "1_1") (pintype "power_in"))
      (node (ref "R21") (pin "1") (pinfunction "1_1") (pintype "passive"))
      (node (ref "R27") (pin "2") (pinfunction "2_2") (pintype "passive"))
      (node (ref "X3") (pin "1") (pinfunction "1_1") (pintype "passive"))
    )
    (net (code "15") (name "Net-(C10-Pad1)") (class "Default")
      (node (ref "C10") (pin "1") (pinfunction "1_1") (pintype "power_in"))
      (node (ref "C8") (pin "1") (pinfunction "1_1") (pintype "power_in"))
      (node (ref "C9") (pin "1") (pinfunction "1_1") (pintype "power_in"))
      (node (ref "R24") (pin "2") (pinfunction "2_2") (pintype "passive"))
      (node (ref "R28") (pin "2") (pinfunction "2_2") (pintype "passive"))
      (node (ref "X4") (pin "1") (pinfunction "1_1") (pintype "passive"))
    )
    (net (code "16") (name "Net-(C13-Pad1)") (class "Default")
      (node (ref "C13") (pin "1") (pinfunction "1_1") (pintype "power_in"))
      (node (ref "R29") (pin "2") (pinfunction "2_2") (pintype "passive"))
      (node (ref "R30") (pin "1") (pinfunction "1_1") (pintype "passive"))
    )
    (net (code "17") (name "Net-(C13-Pad2)") (class "Default")
      (node (ref "C13") (pin "2") (pinfunction "2_2") (pintype "power_in"))
      (node (ref "R21") (pin "2") (pinfunction "2_2") (pintype "passive"))
      (node (ref "R22") (pin "1") (pinfunction "1_1") (pintype "passive"))
    )
    (net (code "18") (name "Net-(C14-Pad1)") (class "Default")
      (node (ref "C14") (pin "1") (pinfunction "1_1") (pintype "power_in"))
      (node (ref "R31") (pin "2") (pinfunction "2_2") (pintype "passive"))
      (node (ref "R32") (pin "1") (pinfunction "1_1") (pintype "passive"))
    )
    (net (code "19") (name "Net-(C14-Pad2)") (class "Default")
      (node (ref "C14") (pin "2") (pinfunction "2_2") (pintype "power_in"))
      (node (ref "R23") (pin "2") (pinfunction "2_2") (pintype "passive"))
      (node (ref "R24") (pin "1") (pinfunction "1_1") (pintype "passive"))
    )
    (net (code "20") (name "Net-(D1-HO)") (class "Default")
      (node (ref "D1") (pin "3") (pinfunction "HO_3") (pintype "output"))
      (node (ref "R1") (pin "1") (pinfunction "1_1") (pintype "passive"))
    )
    (net (code "21") (name "Net-(D1-LO)") (class "Default")
      (node (ref "D1") (pin "10") (pinfunction "LO_10") (pintype "output"))
      (node (ref "R5") (pin "1") (pinfunction "1_1") (pintype "passive"))
    )
    (net (code "22") (name "Net-(D1-RDT)") (class "Default")
      (node (ref "D1") (pin "6") (pinfunction "RDT_6") (pintype "passive"))
      (node (ref "R9") (pin "2") (pinfunction "2_2") (pintype "passive"))
    )
    (net (code "23") (name "Net-(D1-VB)") (class "Default")
      (node (ref "C1") (pin "2") (pinfunction "2_2") (pintype "power_in"))
      (node (ref "D1") (pin "2") (pinfunction "VB_2") (pintype "passive"))
      (node (ref "VD1") (pin "2") (pinfunction "2_2") (pintype "passive"))
    )
    (net (code "24") (name "Net-(D1-VS)") (class "Default")
      (node (ref "C1") (pin "1") (pinfunction "1_1") (pintype "power_in"))
      (node (ref "D1") (pin "4") (pinfunction "VS_4") (pintype "passive"))
      (node (ref "L1") (pin "2") (pinfunction "2_2") (pintype "passive"))
      (node (ref "R3") (pin "1") (pinfunction "1_1") (pintype "passive"))
      (node (ref "VT1") (pin "3") (pinfunction "S_3") (pintype "passive"))
      (node (ref "VT3") (pin "2") (pinfunction "D_2") (pintype "passive"))
    )
    (net (code "25") (name "Net-(D2-HO)") (class "Default")
      (node (ref "D2") (pin "3") (pinfunction "HO_3") (pintype "output"))
      (node (ref "R2") (pin "2") (pinfunction "2_2") (pintype "passive"))
    )
    (net (code "26") (name "Net-(D2-LO)") (class "Default")
      (node (ref "D2") (pin "10") (pinfunction "LO_10") (pintype "output"))
      (node (ref "R6") (pin "2") (pinfunction "2_2") (pintype "passive"))
    )
    (net (code "27") (name "Net-(D2-RDT)") (class "Default")
      (node (ref "D2") (pin "6") (pinfunction "RDT_6") (pintype "passive"))
      (node (ref "R10") (pin "2") (pinfunction "2_2") (pintype "passive"))
    )
    (net (code "28") (name "Net-(D2-VB)") (class "Default")
      (node (ref "C2") (pin "2") (pinfunction "2_2") (pintype "power_in"))
      (node (ref "D2") (pin "2") (pinfunction "VB_2") (pintype "passive"))
      (node (ref "VD2") (pin "2") (pinfunction "2_2") (pintype "passive"))
    )
    (net (code "29") (name "Net-(D2-VS)") (class "Default")
      (node (ref "C2") (pin "1") (pinfunction "1_1") (pintype "power_in"))
      (node (ref "D2") (pin "4") (pinfunction "VS_4") (pintype "passive"))
      (node (ref "L1") (pin "1") (pinfunction "1_1") (pintype "passive"))
      (node (ref "R4") (pin "1") (pinfunction "1_1") (pintype "passive"))
      (node (ref "VT2") (pin "3") (pinfunction "S_3") (pintype "passive"))
      (node (ref "VT4") (pin "2") (pinfunction "D_2") (pintype "passive"))
    )
    (net (code "30") (name "Net-(D3-IN+)") (class "Default")
      (node (ref "D3") (pin "3") (pinfunction "IN+_3") (pintype "input"))
      (node (ref "R19") (pin "1") (pinfunction "1_1") (pintype "passive"))
      (node (ref "R22") (pin "2") (pinfunction "2_2") (pintype "passive"))
    )
    (net (code "31") (name "Net-(D3-IN-)") (class "Default")
      (node (ref "D3") (pin "4") (pinfunction "IN-_4") (pintype "input"))
      (node (ref "R30") (pin "2") (pinfunction "2_2") (pintype "passive"))
      (node (ref "R33") (pin "1") (pinfunction "1_1") (pintype "passive"))
    )
    (net (code "32") (name "Net-(D3-OUT)") (class "Default")
      (node (ref "D3") (pin "1") (pinfunction "OUT_1") (pintype "power_in"))
      (node (ref "R25") (pin "1") (pinfunction "1_1") (pintype "passive"))
      (node (ref "R33") (pin "2") (pinfunction "2_2") (pintype "passive"))
    )
    (net (code "33") (name "Net-(D4-IN+)") (class "Default")
      (node (ref "D4") (pin "3") (pinfunction "IN+_3") (pintype "input"))
      (node (ref "R20") (pin "1") (pinfunction "1_1") (pintype "passive"))
      (node (ref "R23") (pin "1") (pinfunction "1_1") (pintype "passive"))
    )
    (net (code "34") (name "Net-(D4-IN-)") (class "Default")
      (node (ref "D4") (pin "4") (pinfunction "IN-_4") (pintype "input"))
      (node (ref "R31") (pin "1") (pinfunction "1_1") (pintype "passive"))
      (node (ref "R34") (pin "2") (pinfunction "2_2") (pintype "passive"))
    )
    (net (code "35") (name "Net-(D4-OUT)") (class "Default")
      (node (ref "D4") (pin "1") (pinfunction "OUT_1") (pintype "power_in"))
      (node (ref "R26") (pin "2") (pinfunction "2_2") (pintype "passive"))
      (node (ref "R34") (pin "1") (pinfunction "1_1") (pintype "passive"))
    )
    (net (code "36") (name "Net-(D5-FB)") (class "Default")
      (node (ref "D5") (pin "3") (pinfunction "FB_3") (pintype "input"))
      (node (ref "R38") (pin "2") (pinfunction "2_2") (pintype "passive"))
      (node (ref "R39") (pin "2") (pinfunction "2_2") (pintype "passive"))
    )
    (net (code "37") (name "Net-(D5-SW)") (class "Default")
      (node (ref "D5") (pin "1") (pinfunction "SW_1") (pintype "passive"))
      (node (ref "L2") (pin "1") (pinfunction "1_1") (pintype "passive"))
      (node (ref "VD3") (pin "1") (pinfunction "1_1") (pintype "passive"))
    )
    (net (code "38") (name "Net-(D5-~{SHDN})") (class "Default")
      (node (ref "D5") (pin "4") (pinfunction "~{SHDN}_4") (pintype "input"))
      (node (ref "R35") (pin "1") (pinfunction "1_1") (pintype "passive"))
    )
    (net (code "39") (name "Net-(VD4-A)") (class "Default")
      (node (ref "R36") (pin "1") (pinfunction "1_1") (pintype "passive"))
      (node (ref "VD4") (pin "1") (pinfunction "A_1") (pintype "passive"))
    )
    (net (code "40") (name "Net-(VD5-A)") (class "Default")
      (node (ref "R37") (pin "1") (pinfunction "1_1") (pintype "passive"))
      (node (ref "VD5") (pin "1") (pinfunction "A_1") (pintype "passive"))
    )
    (net (code "41") (name "Net-(VT1-G)") (class "Default")
      (node (ref "R1") (pin "2") (pinfunction "2_2") (pintype "passive"))
      (node (ref "R3") (pin "2") (pinfunction "2_2") (pintype "passive"))
      (node (ref "VT1") (pin "1") (pinfunction "G_1") (pintype "passive"))
    )
    (net (code "42") (name "Net-(VT2-G)") (class "Default")
      (node (ref "R2") (pin "1") (pinfunction "1_1") (pintype "passive"))
      (node (ref "R4") (pin "2") (pinfunction "2_2") (pintype "passive"))
      (node (ref "VT2") (pin "1") (pinfunction "G_1") (pintype "passive"))
    )
    (net (code "43") (name "Net-(VT3-G)") (class "Default")
      (node (ref "R13") (pin "2") (pinfunction "2_2") (pintype "passive"))
      (node (ref "R5") (pin "2") (pinfunction "2_2") (pintype "passive"))
      (node (ref "VT3") (pin "1") (pinfunction "G_1") (pintype "passive"))
    )
    (net (code "44") (name "Net-(VT4-G)") (class "Default")
      (node (ref "R14") (pin "2") (pinfunction "2_2") (pintype "passive"))
      (node (ref "R6") (pin "1") (pinfunction "1_1") (pintype "passive"))
      (node (ref "VT4") (pin "1") (pinfunction "G_1") (pintype "passive"))
    )
  )
)
